# boost.net
KiCad netlist of a schematic drawn in Altium Designer
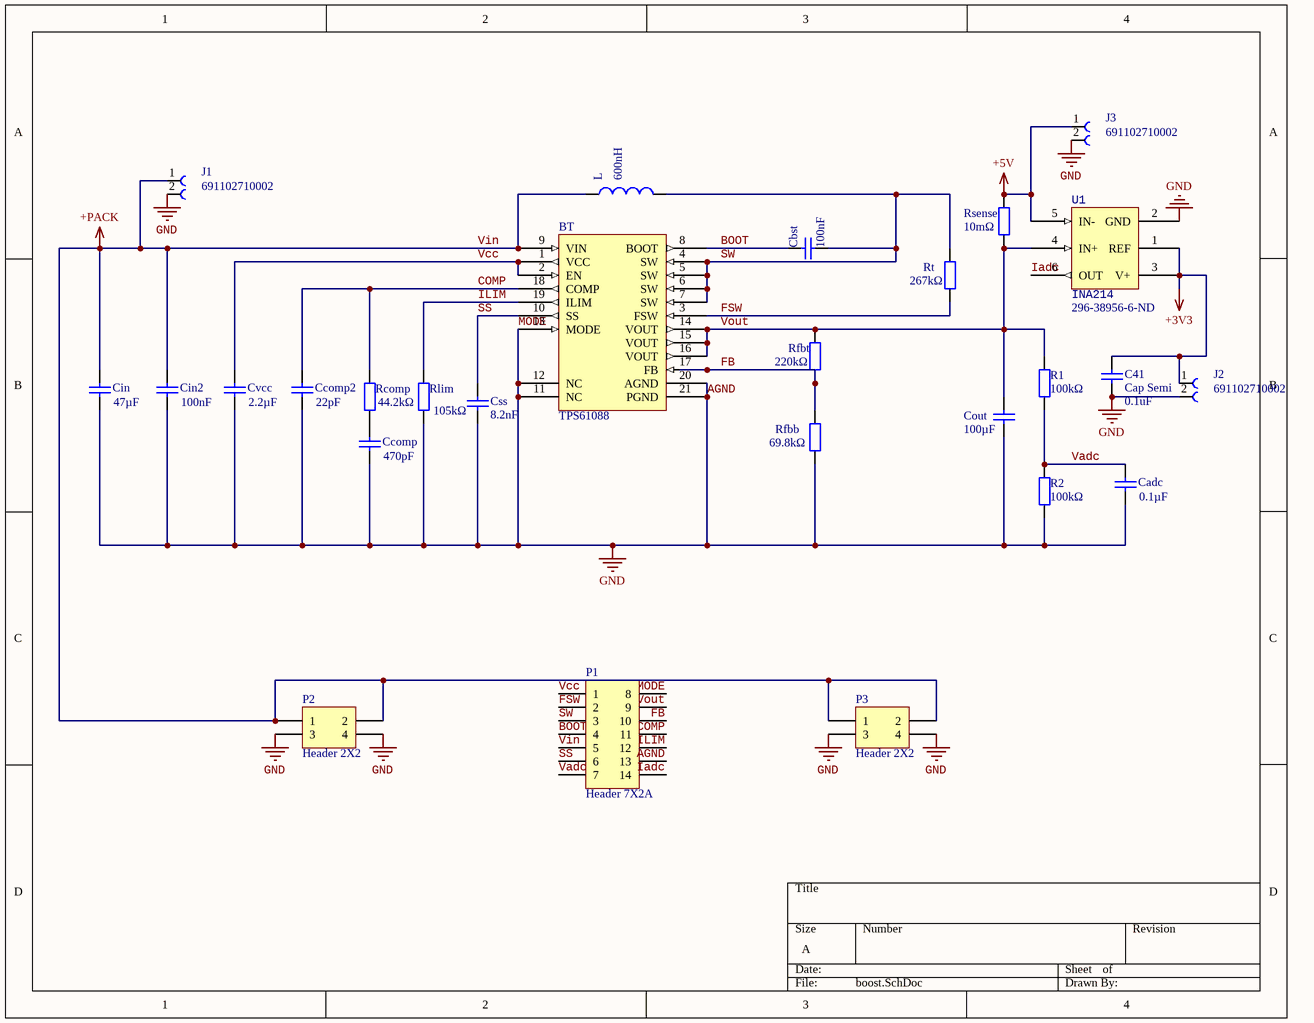
[diagram p0: boost.SchDoc]

(export (version "E")
  (design (tool "Eeschema 10.0.6"))
  (components
    (comp (ref "BT")
      (value "TPS61088")
      (footprint "QFN50P450X350X100-21N")
      (description "Boost converter")
      (libsource (lib "heron-general") (part "TPS61088"))
    )
    (comp (ref "C41")
      (value "Cap Semi")
      (footprint "0603")
      (description "Capacitor (Semiconductor SIM Model)")
      (fields (field (name "ALTIUM_VALUE") "0.1uF") (field (name "PUBLISHER") "Altium Limited"))
      (libsource (lib "Miscellaneous Devices") (part "Cap Semi"))
    )
    (comp (ref "Cadc")
      (value "0.1µF")
      (footprint "0603")
      (description "Capacitor")
      (fields (field (name "PUBLISHER") "Altium Limited"))
      (libsource (lib "Miscellaneous Devices") (part "Cap"))
    )
    (comp (ref "Cbst")
      (value "100nF")
      (footprint "0603")
      (description "Capacitor")
      (fields (field (name "PUBLISHER") "Altium Limited"))
      (libsource (lib "Miscellaneous Devices") (part "Cap"))
    )
    (comp (ref "Ccomp")
      (value "470pF")
      (footprint "0603")
      (description "Capacitor")
      (fields (field (name "PUBLISHER") "Altium Limited"))
      (libsource (lib "Miscellaneous Devices") (part "Cap"))
    )
    (comp (ref "Ccomp2")
      (value "22pF")
      (footprint "0805")
      (description "Capacitor")
      (fields (field (name "PUBLISHER") "Altium Limited"))
      (libsource (lib "Miscellaneous Devices") (part "Cap"))
    )
    (comp (ref "Cin")
      (value "47µF")
      (footprint "1210")
      (description "Capacitor")
      (fields (field (name "PUBLISHER") "Altium Limited"))
      (libsource (lib "Miscellaneous Devices") (part "Cap"))
    )
    (comp (ref "Cin2")
      (value "100nF")
      (footprint "0603")
      (description "Capacitor")
      (fields (field (name "PUBLISHER") "Altium Limited"))
      (libsource (lib "Miscellaneous Devices") (part "Cap"))
    )
    (comp (ref "Cout")
      (value "100µF")
      (footprint "1210")
      (description "Capacitor")
      (fields (field (name "PUBLISHER") "Altium Limited"))
      (libsource (lib "Miscellaneous Devices") (part "Cap"))
    )
    (comp (ref "Css")
      (value "8.2nF")
      (footprint "0805")
      (description "Capacitor")
      (fields (field (name "PUBLISHER") "Altium Limited"))
      (libsource (lib "Miscellaneous Devices") (part "Cap"))
    )
    (comp (ref "Cvcc")
      (value "2.2µF")
      (footprint "0805")
      (description "Capacitor")
      (fields (field (name "PUBLISHER") "Altium Limited"))
      (libsource (lib "Miscellaneous Devices") (part "Cap"))
    )
    (comp (ref "J1")
      (value "691102710002")
      (footprint "691102710002:691102710002")
      (description "102 Series 5mm Pitch Straight, PCB Terminal Block, Through Hole, 2 Way")
      (fields (field (name "MF") "Wurth Electronics"))
      (libsource (lib "691102710002") (part "691102710002"))
    )
    (comp (ref "J2")
      (value "691102710002")
      (footprint "691102710002:691102710002")
      (description "102 Series 5mm Pitch Straight, PCB Terminal Block, Through Hole, 2 Way")
      (fields (field (name "MF") "Wurth Electronics"))
      (libsource (lib "691102710002") (part "691102710002"))
    )
    (comp (ref "J3")
      (value "691102710002")
      (footprint "691102710002:691102710002")
      (description "102 Series 5mm Pitch Straight, PCB Terminal Block, Through Hole, 2 Way")
      (fields (field (name "MF") "Wurth Electronics"))
      (libsource (lib "691102710002") (part "691102710002"))
    )
    (comp (ref "L")
      (value "600nH")
      (footprint "2-SMD")
      (description "Inductor")
      (fields (field (name "PUBLISHER") "Altium Limited"))
      (libsource (lib "Miscellaneous Devices") (part "Inductor"))
    )
    (comp (ref "P1")
      (value "Header 7X2A")
      (footprint "HDR2X7_CEN")
      (description "Header, 7-Pin, Dual row")
      (fields (field (name "PUBLISHER") "Altium Limited"))
      (libsource (lib "Miscellaneous Connectors") (part "Header 7X2A"))
    )
    (comp (ref "P2")
      (value "Header 2X2")
      (footprint "HDR2X2")
      (description "Header, 2-Pin, Dual row")
      (fields (field (name "PUBLISHER") "Altium Limited"))
      (libsource (lib "Miscellaneous Connectors") (part "Header 2X2"))
    )
    (comp (ref "P3")
      (value "Header 2X2")
      (footprint "HDR2X2")
      (description "Header, 2-Pin, Dual row")
      (fields (field (name "PUBLISHER") "Altium Limited"))
      (libsource (lib "Miscellaneous Connectors") (part "Header 2X2"))
    )
    (comp (ref "R1")
      (value "100kΩ")
      (footprint "0603")
      (description "Resistor")
      (fields (field (name "PUBLISHER") "Altium Limited"))
      (libsource (lib "") (part "Res2_1"))
    )
    (comp (ref "R2")
      (value "100kΩ")
      (footprint "0603")
      (description "Resistor")
      (fields (field (name "PUBLISHER") "Altium Limited"))
      (libsource (lib "") (part "Res2_1"))
    )
    (comp (ref "Rcomp")
      (value "44.2kΩ")
      (footprint "0805")
      (description "Resistor")
      (fields (field (name "PUBLISHER") "Altium Limited"))
      (libsource (lib "") (part "Res2_1"))
    )
    (comp (ref "Rfbb")
      (value "69.8kΩ")
      (footprint "0805")
      (description "Resistor")
      (fields (field (name "PUBLISHER") "Altium Limited"))
      (libsource (lib "") (part "Res2_1"))
    )
    (comp (ref "Rfbt")
      (value "220kΩ")
      (footprint "0805")
      (description "Resistor")
      (fields (field (name "PUBLISHER") "Altium Limited"))
      (libsource (lib "") (part "Res2_1"))
    )
    (comp (ref "Rlim")
      (value "105kΩ")
      (footprint "0603")
      (description "Resistor")
      (fields (field (name "PUBLISHER") "Altium Limited"))
      (libsource (lib "") (part "Res2_1"))
    )
    (comp (ref "Rsense")
      (value "10mΩ")
      (footprint "0805")
      (description "Resistor")
      (fields (field (name "Comment") "10mΩ 1/2W 0805") (field (name "PUBLISHER") "Altium Limited"))
      (libsource (lib "") (part "Res2_1"))
    )
    (comp (ref "Rt")
      (value "267kΩ")
      (footprint "0603")
      (description "Resistor")
      (fields (field (name "Comment") "RtA1") (field (name "PUBLISHER") "Altium Limited"))
      (libsource (lib "Miscellaneous Devices") (part "Res2"))
    )
    (comp (ref "U1")
      (value "INA214")
      (footprint "SOT65P210X110-6N")
      (description "Current monitor")
      (fields (field (name "SUPPLIER PART NUMBER 1") "296-38956-6-ND"))
      (libsource (lib "heron-general") (part "INA214"))
    )
  )
  (nets
    (net (code "1") (name "+3V3") (class "Default")
      (node (ref "C41") (pin "2") (pinfunction "2_2") (pintype "passive"))
      (node (ref "J2") (pin "1") (pinfunction "1_1") (pintype "passive"))
      (node (ref "U1") (pin "1") (pinfunction "REF_1") (pintype "passive"))
      (node (ref "U1") (pin "3") (pinfunction "V+_3") (pintype "power_in"))
    )
    (net (code "2") (name "+5V") (class "Default")
      (node (ref "J3") (pin "1") (pinfunction "1_1") (pintype "passive"))
      (node (ref "Rsense") (pin "2") (pinfunction "2_2") (pintype "passive"))
      (node (ref "U1") (pin "5") (pinfunction "IN-_5") (pintype "input"))
    )
    (net (code "3") (name "+PACK") (class "Default")
      (node (ref "BT") (pin "9") (pinfunction "VIN_9") (pintype "input"))
      (node (ref "Cin") (pin "2") (pinfunction "2_2") (pintype "passive"))
      (node (ref "Cin2") (pin "2") (pinfunction "2_2") (pintype "passive"))
      (node (ref "J1") (pin "1") (pinfunction "1_1") (pintype "passive"))
      (node (ref "L") (pin "1") (pinfunction "1_1") (pintype "passive"))
      (node (ref "P1") (pin "5") (pinfunction "5_5") (pintype "passive"))
      (node (ref "P2") (pin "1") (pinfunction "1_1") (pintype "passive"))
      (node (ref "P2") (pin "2") (pinfunction "2_2") (pintype "passive"))
      (node (ref "P3") (pin "1") (pinfunction "1_1") (pintype "passive"))
      (node (ref "P3") (pin "2") (pinfunction "2_2") (pintype "passive"))
    )
    (net (code "4") (name "/BOOT") (class "Default")
      (node (ref "BT") (pin "8") (pinfunction "BOOT_8") (pintype "output"))
      (node (ref "Cbst") (pin "2") (pinfunction "2_2") (pintype "passive"))
      (node (ref "P1") (pin "4") (pinfunction "4_4") (pintype "passive"))
    )
    (net (code "5") (name "/COMP") (class "Default")
      (node (ref "BT") (pin "18") (pinfunction "COMP_18") (pintype "output"))
      (node (ref "Ccomp2") (pin "2") (pinfunction "2_2") (pintype "passive"))
      (node (ref "P1") (pin "11") (pinfunction "11_11") (pintype "passive"))
      (node (ref "Rcomp") (pin "2") (pinfunction "2_2") (pintype "passive"))
    )
    (net (code "6") (name "/FB") (class "Default")
      (node (ref "BT") (pin "17") (pinfunction "FB_17") (pintype "input"))
      (node (ref "P1") (pin "10") (pinfunction "10_10") (pintype "passive"))
      (node (ref "Rfbb") (pin "2") (pinfunction "2_2") (pintype "passive"))
      (node (ref "Rfbt") (pin "1") (pinfunction "1_1") (pintype "passive"))
    )
    (net (code "7") (name "/FSW") (class "Default")
      (node (ref "BT") (pin "3") (pinfunction "FSW_3") (pintype "input"))
      (node (ref "P1") (pin "2") (pinfunction "2_2") (pintype "passive"))
      (node (ref "Rt") (pin "2") (pinfunction "2_2") (pintype "passive"))
    )
    (net (code "8") (name "/ILIM") (class "Default")
      (node (ref "BT") (pin "19") (pinfunction "ILIM_19") (pintype "output"))
      (node (ref "P1") (pin "12") (pinfunction "12_12") (pintype "passive"))
      (node (ref "Rlim") (pin "2") (pinfunction "2_2") (pintype "passive"))
    )
    (net (code "9") (name "/Iadc") (class "Default")
      (node (ref "P1") (pin "14") (pinfunction "14_14") (pintype "passive"))
      (node (ref "U1") (pin "6") (pinfunction "OUT_6") (pintype "output"))
    )
    (net (code "10") (name "/SS") (class "Default")
      (node (ref "BT") (pin "10") (pinfunction "SS_10") (pintype "output"))
      (node (ref "Css") (pin "2") (pinfunction "2_2") (pintype "passive"))
      (node (ref "P1") (pin "6") (pinfunction "6_6") (pintype "passive"))
    )
    (net (code "11") (name "/SW") (class "Default")
      (node (ref "BT") (pin "4") (pinfunction "SW_4") (pintype "input"))
      (node (ref "BT") (pin "5") (pinfunction "SW_5") (pintype "input"))
      (node (ref "BT") (pin "6") (pinfunction "SW_6") (pintype "input"))
      (node (ref "BT") (pin "7") (pinfunction "SW_7") (pintype "input"))
      (node (ref "Cbst") (pin "1") (pinfunction "1_1") (pintype "passive"))
      (node (ref "L") (pin "2") (pinfunction "2_2") (pintype "passive"))
      (node (ref "P1") (pin "3") (pinfunction "3_3") (pintype "passive"))
      (node (ref "Rt") (pin "1") (pinfunction "1_1") (pintype "passive"))
    )
    (net (code "12") (name "/Vadc") (class "Default")
      (node (ref "Cadc") (pin "1") (pinfunction "1_1") (pintype "passive"))
      (node (ref "P1") (pin "7") (pinfunction "7_7") (pintype "passive"))
      (node (ref "R1") (pin "1") (pinfunction "1_1") (pintype "passive"))
      (node (ref "R2") (pin "2") (pinfunction "2_2") (pintype "passive"))
    )
    (net (code "13") (name "/Vcc") (class "Default")
      (node (ref "BT") (pin "1") (pinfunction "VCC_1") (pintype "output"))
      (node (ref "BT") (pin "2") (pinfunction "EN_2") (pintype "input"))
      (node (ref "Cvcc") (pin "2") (pinfunction "2_2") (pintype "passive"))
      (node (ref "P1") (pin "1") (pinfunction "1_1") (pintype "passive"))
    )
    (net (code "14") (name "/Vout") (class "Default")
      (node (ref "BT") (pin "14") (pinfunction "VOUT_14") (pintype "output"))
      (node (ref "BT") (pin "15") (pinfunction "VOUT_15") (pintype "output"))
      (node (ref "BT") (pin "16") (pinfunction "VOUT_16") (pintype "output"))
      (node (ref "Cout") (pin "2") (pinfunction "2_2") (pintype "passive"))
      (node (ref "P1") (pin "9") (pinfunction "9_9") (pintype "passive"))
      (node (ref "R1") (pin "2") (pinfunction "2_2") (pintype "passive"))
      (node (ref "Rfbt") (pin "2") (pinfunction "2_2") (pintype "passive"))
      (node (ref "Rsense") (pin "1") (pinfunction "1_1") (pintype "passive"))
      (node (ref "U1") (pin "4") (pinfunction "IN+_4") (pintype "input"))
    )
    (net (code "15") (name "GND") (class "Default")
      (node (ref "BT") (pin "11") (pinfunction "NC_11") (pintype "passive"))
      (node (ref "BT") (pin "12") (pinfunction "NC_12") (pintype "passive"))
      (node (ref "BT") (pin "13") (pinfunction "MODE_13") (pintype "input"))
      (node (ref "BT") (pin "20") (pinfunction "AGND_20") (pintype "power_in"))
      (node (ref "BT") (pin "21") (pinfunction "PGND_21") (pintype "power_in"))
      (node (ref "C41") (pin "1") (pinfunction "1_1") (pintype "passive"))
      (node (ref "Cadc") (pin "2") (pinfunction "2_2") (pintype "passive"))
      (node (ref "Ccomp") (pin "1") (pinfunction "1_1") (pintype "passive"))
      (node (ref "Ccomp2") (pin "1") (pinfunction "1_1") (pintype "passive"))
      (node (ref "Cin") (pin "1") (pinfunction "1_1") (pintype "passive"))
      (node (ref "Cin2") (pin "1") (pinfunction "1_1") (pintype "passive"))
      (node (ref "Cout") (pin "1") (pinfunction "1_1") (pintype "passive"))
      (node (ref "Css") (pin "1") (pinfunction "1_1") (pintype "passive"))
      (node (ref "Cvcc") (pin "1") (pinfunction "1_1") (pintype "passive"))
      (node (ref "J1") (pin "2") (pinfunction "2_2") (pintype "passive"))
      (node (ref "J2") (pin "2") (pinfunction "2_2") (pintype "passive"))
      (node (ref "J3") (pin "2") (pinfunction "2_2") (pintype "passive"))
      (node (ref "P1") (pin "13") (pinfunction "13_13") (pintype "passive"))
      (node (ref "P1") (pin "8") (pinfunction "8_8") (pintype "passive"))
      (node (ref "P2") (pin "3") (pinfunction "3_3") (pintype "passive"))
      (node (ref "P2") (pin "4") (pinfunction "4_4") (pintype "passive"))
      (node (ref "P3") (pin "3") (pinfunction "3_3") (pintype "passive"))
      (node (ref "P3") (pin "4") (pinfunction "4_4") (pintype "passive"))
      (node (ref "R2") (pin "1") (pinfunction "1_1") (pintype "passive"))
      (node (ref "Rfbb") (pin "1") (pinfunction "1_1") (pintype "passive"))
      (node (ref "Rlim") (pin "1") (pinfunction "1_1") (pintype "passive"))
      (node (ref "U1") (pin "2") (pinfunction "GND_2") (pintype "power_in"))
    )
    (net (code "16") (name "Net-(Ccomp-Pad2)") (class "Default")
      (node (ref "Ccomp") (pin "2") (pinfunction "2_2") (pintype "passive"))
      (node (ref "Rcomp") (pin "1") (pinfunction "1_1") (pintype "passive"))
    )
  )
)
